# Support.net
KiCad netlist of a schematic drawn in Altium Designer
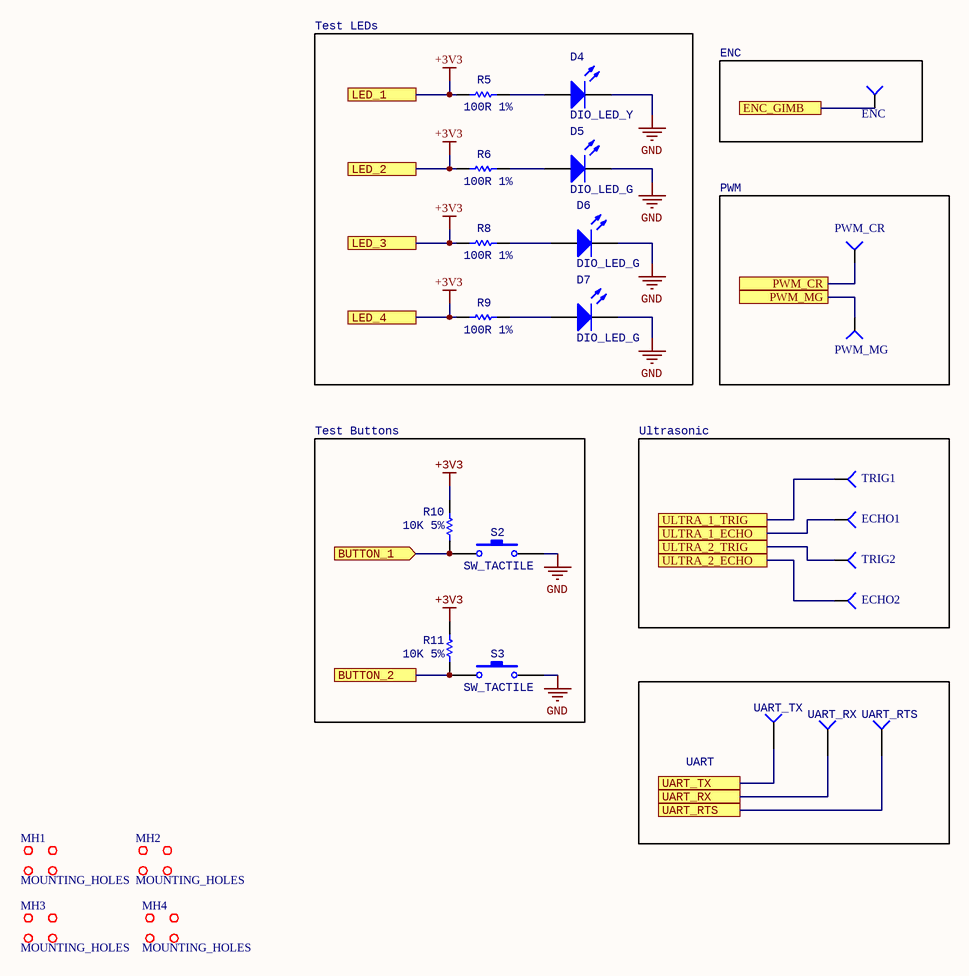
[diagram p0: Support.SchDoc]

(export (version "E")
  (design (tool "Eeschema 10.0.6"))
  (components
    (comp (ref "D4")
      (value "DIO_LED_Y")
      (footprint "LED_0805_LINE")
      (description "LED YELLOW DIFFUSED 0805 SMD")
      (fields (field (name "MANUFACTURER") "OSRAM") (field (name "MPN") "LY R976-PS-36"))
      (libsource (lib "UWRT_Schematic_Library_2020") (part "DIO_LED_Y"))
    )
    (comp (ref "D5")
      (value "DIO_LED_G")
      (footprint "LED_0805_LINE")
      (description "LED GREEN DIFFUSED 0805 SMD")
      (fields (field (name "MANUFACTURER") "OSRAM") (field (name "MPN") "LG R971-KN-1"))
      (libsource (lib "UWRT_Schematic_Library_2020") (part "DIO_LED_G"))
    )
    (comp (ref "D6")
      (value "DIO_LED_G")
      (footprint "LED_0805_LINE")
      (description "LED GREEN DIFFUSED 0805 SMD")
      (fields (field (name "MANUFACTURER") "OSRAM") (field (name "MPN") "LG R971-KN-1"))
      (libsource (lib "UWRT_Schematic_Library_2020") (part "DIO_LED_G"))
    )
    (comp (ref "D7")
      (value "DIO_LED_G")
      (footprint "LED_0805_LINE")
      (description "LED GREEN DIFFUSED 0805 SMD")
      (fields (field (name "MANUFACTURER") "OSRAM") (field (name "MPN") "LG R971-KN-1"))
      (libsource (lib "UWRT_Schematic_Library_2020") (part "DIO_LED_G"))
    )
    (comp (ref "MH1")
      (value "MOUNTING_HOLES")
      (footprint "MOUNTING_HOLE")
      (description "6cm x 6cm")
      (libsource (lib "UWRT_Schematic_Library_2019") (part "MOUNTING_HOLES"))
    )
    (comp (ref "MH2")
      (value "MOUNTING_HOLES")
      (footprint "MOUNTING_HOLE")
      (description "6cm x 6cm")
      (libsource (lib "UWRT_Schematic_Library_2019") (part "MOUNTING_HOLES"))
    )
    (comp (ref "MH3")
      (value "MOUNTING_HOLES")
      (footprint "MOUNTING_HOLE")
      (description "6cm x 6cm")
      (libsource (lib "UWRT_Schematic_Library_2019") (part "MOUNTING_HOLES"))
    )
    (comp (ref "MH4")
      (value "MOUNTING_HOLES")
      (footprint "MOUNTING_HOLE")
      (description "6cm x 6cm")
      (libsource (lib "UWRT_Schematic_Library_2019") (part "MOUNTING_HOLES"))
    )
    (comp (ref "R5")
      (value "100R 1%")
      (footprint "RESC0603(1608)_N")
      (description "RES SMD 100 OHM 1% 1/10W 0603")
      (fields (field (name "MANUFACTURER") "Yageo") (field (name "TOLERANCE") "1%"))
      (libsource (lib "UWRT_Schematic_Library_2020") (part "RES_100R_0603"))
    )
    (comp (ref "R6")
      (value "100R 1%")
      (footprint "RESC0603(1608)_N")
      (description "RES SMD 100 OHM 1% 1/10W 0603")
      (fields (field (name "MANUFACTURER") "Yageo") (field (name "TOLERANCE") "1%"))
      (libsource (lib "UWRT_Schematic_Library_2020") (part "RES_100R_0603"))
    )
    (comp (ref "R8")
      (value "100R 1%")
      (footprint "RESC0603(1608)_N")
      (description "RES SMD 100 OHM 1% 1/10W 0603")
      (fields (field (name "MANUFACTURER") "Yageo") (field (name "TOLERANCE") "1%"))
      (libsource (lib "UWRT_Schematic_Library_2020") (part "RES_100R_0603"))
    )
    (comp (ref "R9")
      (value "100R 1%")
      (footprint "RESC0603(1608)_N")
      (description "RES SMD 100 OHM 1% 1/10W 0603")
      (fields (field (name "MANUFACTURER") "Yageo") (field (name "TOLERANCE") "1%"))
      (libsource (lib "UWRT_Schematic_Library_2020") (part "RES_100R_0603"))
    )
    (comp (ref "R10")
      (value "10K 5%")
      (footprint "RESC0603(1608)_N")
      (description "RES SMD 10K OHM 5% 1/10W 0603")
      (fields (field (name "MANUFACTURER") "Yageo") (field (name "TOLERANCE") "5%"))
      (libsource (lib "UWRT_Schematic_Library_2020") (part "RES_10K_0603"))
    )
    (comp (ref "R11")
      (value "10K 5%")
      (footprint "RESC0603(1608)_N")
      (description "RES SMD 10K OHM 5% 1/10W 0603")
      (fields (field (name "MANUFACTURER") "Yageo") (field (name "TOLERANCE") "5%"))
      (libsource (lib "UWRT_Schematic_Library_2020") (part "RES_10K_0603"))
    )
    (comp (ref "S2")
      (value "SW_TACTILE")
      (footprint "B3U-1100P")
      (description "Tactile Switch (Grey)")
      (fields (field (name "DIGIKEY PART NUMBER") "SW1021TR-ND") (field (name "MPN") "B3U-1100P"))
      (libsource (lib "UWRT_Schematic_Library_2020") (part "SW_TACTILE"))
    )
    (comp (ref "S3")
      (value "SW_TACTILE")
      (footprint "B3U-1100P")
      (description "Tactile Switch (Grey)")
      (fields (field (name "DIGIKEY PART NUMBER") "SW1021TR-ND") (field (name "MPN") "B3U-1100P"))
      (libsource (lib "UWRT_Schematic_Library_2020") (part "SW_TACTILE"))
    )
    (comp (ref "TP8")
      (value "TRIG1")
      (footprint "TESTPOINT")
      (description "TESTPOINT_SMD")
      (libsource (lib "UWRT_Schematic_Library_2020") (part "TESTPOINT_SMD"))
    )
    (comp (ref "TP9")
      (value "PWM_CR")
      (footprint "TESTPOINT")
      (description "TESTPOINT_SMD")
      (libsource (lib "UWRT_Schematic_Library_2020") (part "TESTPOINT_SMD"))
    )
    (comp (ref "TP10")
      (value "ENC")
      (footprint "TESTPOINT")
      (description "TESTPOINT_SMD")
      (libsource (lib "UWRT_Schematic_Library_2020") (part "TESTPOINT_SMD"))
    )
    (comp (ref "TP11")
      (value "ECHO1")
      (footprint "TESTPOINT")
      (description "TESTPOINT_SMD")
      (libsource (lib "UWRT_Schematic_Library_2020") (part "TESTPOINT_SMD"))
    )
    (comp (ref "TP12")
      (value "TRIG2")
      (footprint "TESTPOINT")
      (description "TESTPOINT_SMD")
      (libsource (lib "UWRT_Schematic_Library_2020") (part "TESTPOINT_SMD"))
    )
    (comp (ref "TP13")
      (value "ECHO2")
      (footprint "TESTPOINT")
      (description "TESTPOINT_SMD")
      (libsource (lib "UWRT_Schematic_Library_2020") (part "TESTPOINT_SMD"))
    )
    (comp (ref "TP14")
      (value "PWM_MG")
      (footprint "TESTPOINT")
      (description "TESTPOINT_SMD")
      (libsource (lib "UWRT_Schematic_Library_2020") (part "TESTPOINT_SMD"))
    )
    (comp (ref "UART_RTS")
      (value "TESTPOINT")
      (libsource (lib "UWRT_Schematic_Library_2019") (part "TESTPOINT"))
    )
    (comp (ref "UART_RX")
      (value "TESTPOINT")
      (libsource (lib "UWRT_Schematic_Library_2019") (part "TESTPOINT"))
    )
    (comp (ref "UART_TX")
      (value "TESTPOINT")
      (libsource (lib "UWRT_Schematic_Library_2019") (part "TESTPOINT"))
    )
  )
  (nets
    (net (code "1") (name "+3V3") (class "Default")
      (node (ref "R10") (pin "1") (pinfunction "1_1") (pintype "passive"))
      (node (ref "R11") (pin "2") (pinfunction "2_2") (pintype "passive"))
      (node (ref "R5") (pin "1") (pinfunction "1_1") (pintype "passive"))
      (node (ref "R6") (pin "1") (pinfunction "1_1") (pintype "passive"))
      (node (ref "R8") (pin "1") (pinfunction "1_1") (pintype "passive"))
      (node (ref "R9") (pin "1") (pinfunction "1_1") (pintype "passive"))
    )
    (net (code "2") (name "/BUTTON_1") (class "Default")
      (node (ref "R10") (pin "2") (pinfunction "2_2") (pintype "passive"))
      (node (ref "S2") (pin "1") (pinfunction "1_1") (pintype "passive"))
    )
    (net (code "3") (name "/BUTTON_2") (class "Default")
      (node (ref "R11") (pin "1") (pinfunction "1_1") (pintype "passive"))
      (node (ref "S3") (pin "1") (pinfunction "1_1") (pintype "passive"))
    )
    (net (code "4") (name "/ENC_GIMB") (class "Default")
      (node (ref "TP10") (pin "1") (pinfunction "=value_1") (pintype "passive"))
    )
    (net (code "5") (name "/PWM_CR") (class "Default")
      (node (ref "TP9") (pin "1") (pinfunction "=value_1") (pintype "passive"))
    )
    (net (code "6") (name "/PWM_MG") (class "Default")
      (node (ref "TP14") (pin "1") (pinfunction "=value_1") (pintype "passive"))
    )
    (net (code "7") (name "/UART_RTS") (class "Default")
      (node (ref "UART_RTS") (pin "1") (pinfunction "=value_1") (pintype "passive"))
    )
    (net (code "8") (name "/UART_RX") (class "Default")
      (node (ref "UART_RX") (pin "1") (pinfunction "=value_1") (pintype "passive"))
    )
    (net (code "9") (name "/UART_TX") (class "Default")
      (node (ref "UART_TX") (pin "1") (pinfunction "=value_1") (pintype "passive"))
    )
    (net (code "10") (name "/ULTRA_1_ECHO") (class "Default")
      (node (ref "TP11") (pin "1") (pinfunction "=value_1") (pintype "passive"))
    )
    (net (code "11") (name "/ULTRA_1_TRIG") (class "Default")
      (node (ref "TP8") (pin "1") (pinfunction "=value_1") (pintype "passive"))
    )
    (net (code "12") (name "/ULTRA_2_ECHO") (class "Default")
      (node (ref "TP13") (pin "1") (pinfunction "=value_1") (pintype "passive"))
    )
    (net (code "13") (name "/ULTRA_2_TRIG") (class "Default")
      (node (ref "TP12") (pin "1") (pinfunction "=value_1") (pintype "passive"))
    )
    (net (code "14") (name "GND") (class "Default")
      (node (ref "D4") (pin "2") (pinfunction "K_2") (pintype "passive"))
      (node (ref "D5") (pin "2") (pinfunction "K_2") (pintype "passive"))
      (node (ref "D6") (pin "2") (pinfunction "K_2") (pintype "passive"))
      (node (ref "D7") (pin "2") (pinfunction "K_2") (pintype "passive"))
      (node (ref "S2") (pin "2") (pinfunction "2_2") (pintype "passive"))
      (node (ref "S3") (pin "2") (pinfunction "2_2") (pintype "passive"))
    )
    (net (code "15") (name "Net-(D4-A)") (class "Default")
      (node (ref "D4") (pin "1") (pinfunction "A_1") (pintype "passive"))
      (node (ref "R5") (pin "2") (pinfunction "2_2") (pintype "passive"))
    )
    (net (code "16") (name "Net-(D5-A)") (class "Default")
      (node (ref "D5") (pin "1") (pinfunction "A_1") (pintype "passive"))
      (node (ref "R6") (pin "2") (pinfunction "2_2") (pintype "passive"))
    )
    (net (code "17") (name "Net-(D6-A)") (class "Default")
      (node (ref "D6") (pin "1") (pinfunction "A_1") (pintype "passive"))
      (node (ref "R8") (pin "2") (pinfunction "2_2") (pintype "passive"))
    )
    (net (code "18") (name "Net-(D7-A)") (class "Default")
      (node (ref "D7") (pin "1") (pinfunction "A_1") (pintype "passive"))
      (node (ref "R9") (pin "2") (pinfunction "2_2") (pintype "passive"))
    )
  )
)
